# 08_-_CPU_-_SPI_I2C_SD_MMC.net
KiCad netlist of a schematic drawn in Altium Designer
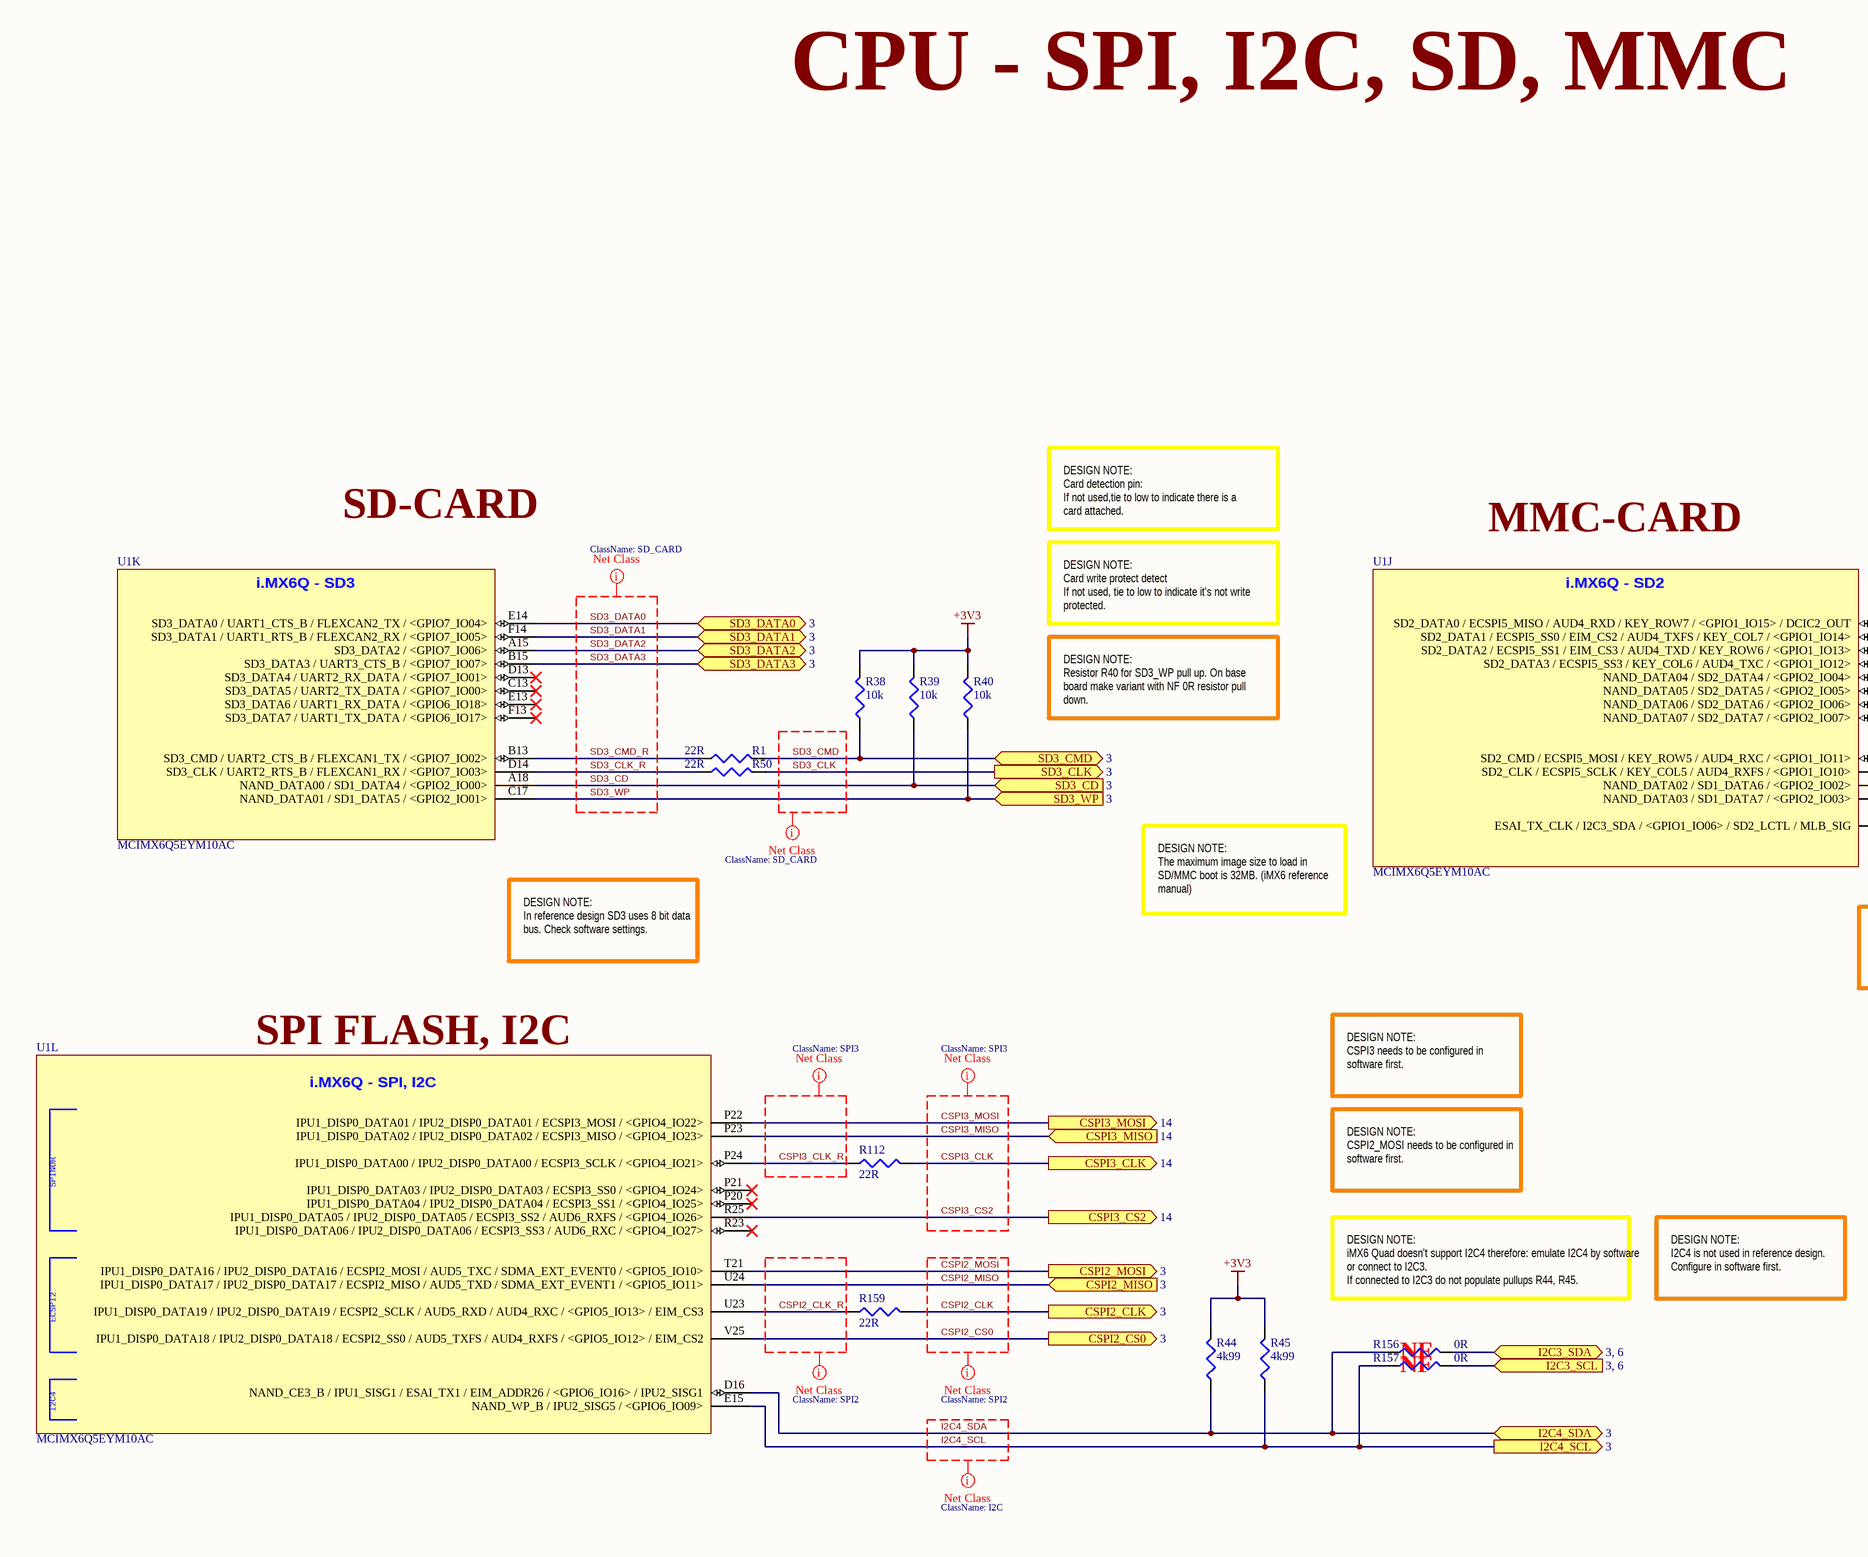
[diagram p0: [08] - CPU - SPI, I2C, SD, MMC.SchDoc, left]
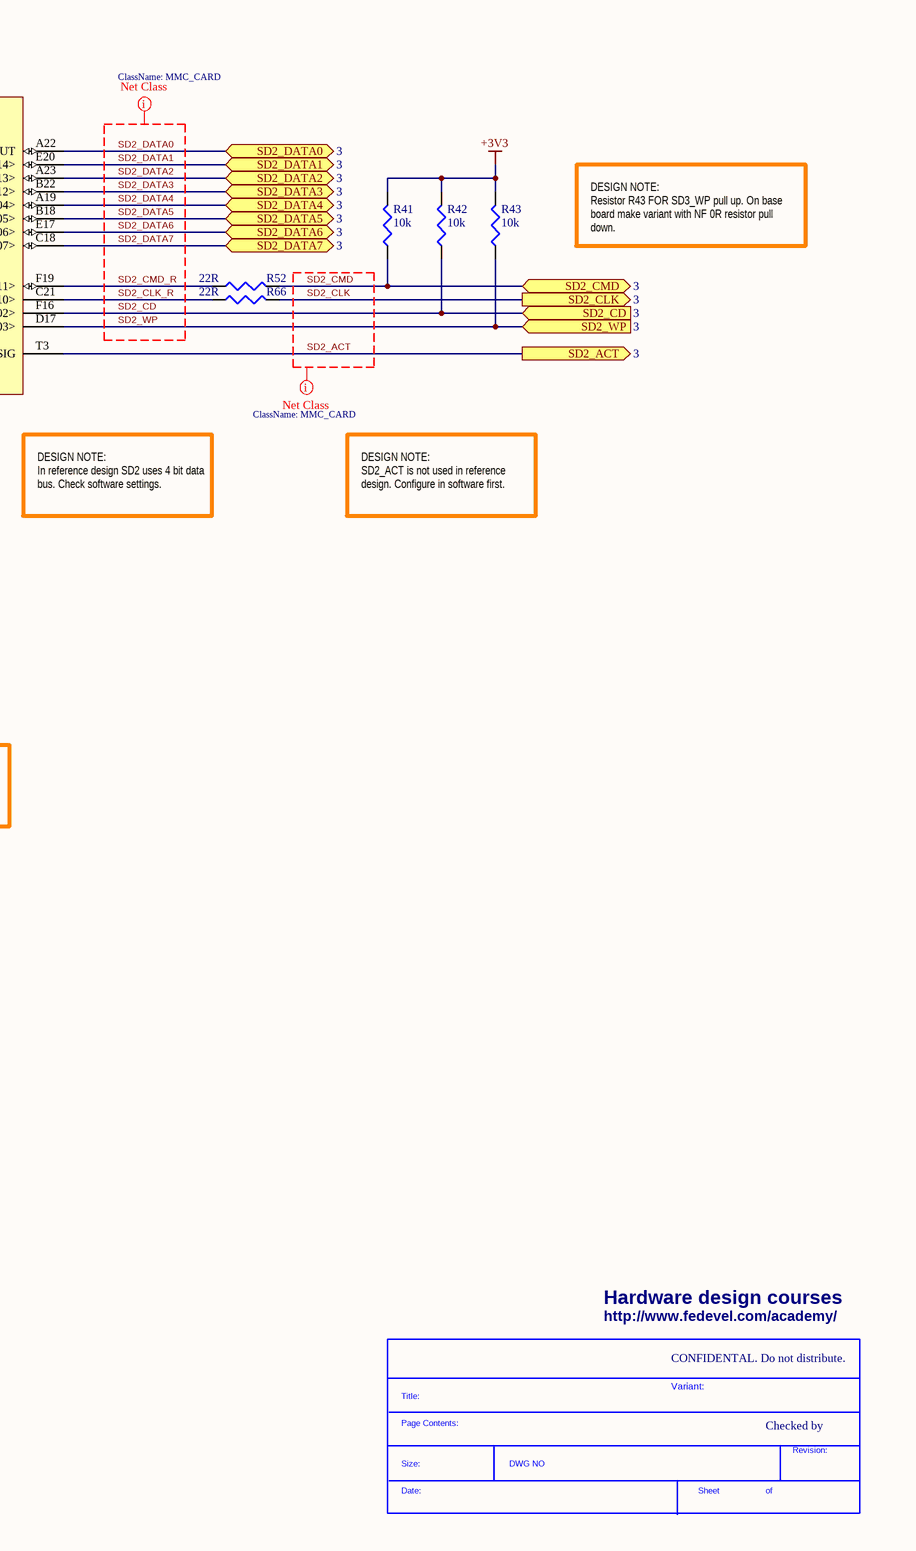
[diagram p1: [08] - CPU - SPI, I2C, SD, MMC.SchDoc, right]

(export (version "E")
  (design (tool "Eeschema 10.0.6"))
  (components
    (comp (ref "R1")
      (value "22R")
      (footprint "R0402")
      (description "RES 22.0 OHM 1/16W 1% 0402 SMD")
      (fields
        (field (name "MANUFACTURER") "Yageo")
        (field (name "MANUFACTURER PART NUMBER") "RC0402FR-0722RL")
      )
      (libsource (lib "iMX6 Rex_V1I1") (part "RC0402FR-0722RL"))
    )
    (comp (ref "R38")
      (value "10k")
      (footprint "R0402")
      (description "RES 10.0K OHM 1/16W 1% 0402 SMD")
      (fields
        (field (name "MANUFACTURER") "Yageo")
        (field (name "MANUFACTURER PART NUMBER") "RC0402FR-0710KL")
      )
      (libsource (lib "iMX6 Rex_V1I1") (part "RC0402FR-0710KL"))
    )
    (comp (ref "R39")
      (value "10k")
      (footprint "R0402")
      (description "RES 10.0K OHM 1/16W 1% 0402 SMD")
      (fields
        (field (name "MANUFACTURER") "Yageo")
        (field (name "MANUFACTURER PART NUMBER") "RC0402FR-0710KL")
      )
      (libsource (lib "iMX6 Rex_V1I1") (part "RC0402FR-0710KL"))
    )
    (comp (ref "R40")
      (value "10k")
      (footprint "R0402")
      (description "RES 10.0K OHM 1/16W 1% 0402 SMD")
      (fields
        (field (name "MANUFACTURER") "Yageo")
        (field (name "MANUFACTURER PART NUMBER") "RC0402FR-0710KL")
      )
      (libsource (lib "iMX6 Rex_V1I1") (part "RC0402FR-0710KL"))
    )
    (comp (ref "R41")
      (value "10k")
      (footprint "R0402")
      (description "RES 10.0K OHM 1/16W 1% 0402 SMD")
      (fields
        (field (name "MANUFACTURER") "Yageo")
        (field (name "MANUFACTURER PART NUMBER") "RC0402FR-0710KL")
      )
      (libsource (lib "iMX6 Rex_V1I1") (part "RC0402FR-0710KL"))
    )
    (comp (ref "R42")
      (value "10k")
      (footprint "R0402")
      (description "RES 10.0K OHM 1/16W 1% 0402 SMD")
      (fields
        (field (name "MANUFACTURER") "Yageo")
        (field (name "MANUFACTURER PART NUMBER") "RC0402FR-0710KL")
      )
      (libsource (lib "iMX6 Rex_V1I1") (part "RC0402FR-0710KL"))
    )
    (comp (ref "R43")
      (value "10k")
      (footprint "R0402")
      (description "RES 10.0K OHM 1/16W 1% 0402 SMD")
      (fields
        (field (name "MANUFACTURER") "Yageo")
        (field (name "MANUFACTURER PART NUMBER") "RC0402FR-0710KL")
      )
      (libsource (lib "iMX6 Rex_V1I1") (part "RC0402FR-0710KL"))
    )
    (comp (ref "R44")
      (value "4k99")
      (footprint "R0402")
      (description "RES TF 4.99K OHM 1% 1/16W 0402")
      (fields
        (field (name "MANUFACTURER") "Stackpole Electronics Inc")
        (field (name "MANUFACTURER PART NUMBER") "RMCF0402FT4K99")
      )
      (libsource (lib "iMX6 Rex_V1I1") (part "RMCF0402FT4K99"))
    )
    (comp (ref "R45")
      (value "4k99")
      (footprint "R0402")
      (description "RES TF 4.99K OHM 1% 1/16W 0402")
      (fields
        (field (name "MANUFACTURER") "Stackpole Electronics Inc")
        (field (name "MANUFACTURER PART NUMBER") "RMCF0402FT4K99")
      )
      (libsource (lib "iMX6 Rex_V1I1") (part "RMCF0402FT4K99"))
    )
    (comp (ref "R50")
      (value "22R")
      (footprint "R0402")
      (description "RES 22.0 OHM 1/16W 1% 0402 SMD")
      (fields
        (field (name "MANUFACTURER") "Yageo")
        (field (name "MANUFACTURER PART NUMBER") "RC0402FR-0722RL")
      )
      (libsource (lib "iMX6 Rex_V1I1") (part "RC0402FR-0722RL"))
    )
    (comp (ref "R52")
      (value "22R")
      (footprint "R0402")
      (description "RES 22.0 OHM 1/16W 1% 0402 SMD")
      (fields
        (field (name "MANUFACTURER") "Yageo")
        (field (name "MANUFACTURER PART NUMBER") "RC0402FR-0722RL")
      )
      (libsource (lib "iMX6 Rex_V1I1") (part "RC0402FR-0722RL"))
    )
    (comp (ref "R66")
      (value "22R")
      (footprint "R0402")
      (description "RES 22.0 OHM 1/16W 1% 0402 SMD")
      (fields
        (field (name "MANUFACTURER") "Yageo")
        (field (name "MANUFACTURER PART NUMBER") "RC0402FR-0722RL")
      )
      (libsource (lib "iMX6 Rex_V1I1") (part "RC0402FR-0722RL"))
    )
    (comp (ref "R112")
      (value "22R")
      (footprint "R0402")
      (description "RES 22.0 OHM 1/16W 1% 0402 SMD")
      (fields
        (field (name "MANUFACTURER") "Yageo")
        (field (name "MANUFACTURER PART NUMBER") "RC0402FR-0722RL")
      )
      (libsource (lib "iMX6 Rex_V1I1") (part "RC0402FR-0722RL"))
    )
    (comp (ref "R156")
      (value "0R")
      (footprint "R0402")
      (description "RES 0.0 OHM 1/16W 0402 SMD")
      (fields
        (field (name "MANUFACTURER") "Yageo")
        (field (name "MANUFACTURER PART NUMBER") "RC0402JR-070RL")
      )
      (libsource (lib "iMX6 Rex_V1I1") (part "RC0402JR-070RL"))
    )
    (comp (ref "R157")
      (value "0R")
      (footprint "R0402")
      (description "RES 0.0 OHM 1/16W 0402 SMD")
      (fields
        (field (name "MANUFACTURER") "Yageo")
        (field (name "MANUFACTURER PART NUMBER") "RC0402JR-070RL")
      )
      (libsource (lib "iMX6 Rex_V1I1") (part "RC0402JR-070RL"))
    )
    (comp (ref "R159")
      (value "22R")
      (footprint "R0402")
      (description "RES 22.0 OHM 1/16W 1% 0402 SMD")
      (fields
        (field (name "MANUFACTURER") "Yageo")
        (field (name "MANUFACTURER PART NUMBER") "RC0402FR-0722RL")
      )
      (libsource (lib "iMX6 Rex_V1I1") (part "RC0402FR-0722RL"))
    )
    (comp (ref "U1")
      (value "MCIMX6Q5EYM10AC")
      (footprint "PBGA624")
      (description "IC MCU 32BIT ARM QUAD 624FCBGA")
      (fields
        (field (name "MANUFACTURER") "Freescale Semiconductor")
        (field (name ".CREATOR") "MM")
        (field (name ".CHECKED PCB") "MM, checked by RF")
        (field (name ".CHECKED SCH") "MM")
      )
      (libsource (lib "iMX6 Rex_V1I1") (part "MCIMX6Q5EYM10AC"))
    )
  )
  (nets
    (net (code "1") (name "+3V3") (class "Default")
      (node (ref "R38") (pin "2") (pinfunction "2_2") (pintype "passive"))
      (node (ref "R39") (pin "2") (pinfunction "2_2") (pintype "passive"))
      (node (ref "R40") (pin "2") (pinfunction "2_2") (pintype "passive"))
      (node (ref "R41") (pin "2") (pinfunction "2_2") (pintype "passive"))
      (node (ref "R42") (pin "2") (pinfunction "2_2") (pintype "passive"))
      (node (ref "R43") (pin "2") (pinfunction "2_2") (pintype "passive"))
      (node (ref "R44") (pin "2") (pinfunction "2_2") (pintype "passive"))
      (node (ref "R45") (pin "2") (pinfunction "2_2") (pintype "passive"))
    )
    (net (code "2") (name "/CSPI2_CLK") (class "Default")
      (node (ref "R159") (pin "2") (pinfunction "2_2") (pintype "passive"))
    )
    (net (code "3") (name "/CSPI2_CLK_R") (class "Default")
      (node (ref "R159") (pin "1") (pinfunction "1_1") (pintype "passive"))
      (node (ref "U1") (pin "U23") (pinfunction "IPU1_DISP0_DATA19_/_IPU2_DISP0_DATA19_/_ECSPI2_SCLK_/_AUD5_RXD_/_AUD4_RXC_/_<GPIO5_IO13>_/_EIM_CS3_U23") (pintype "passive"))
    )
    (net (code "4") (name "/CSPI2_CS0") (class "Default")
      (node (ref "U1") (pin "V25") (pinfunction "IPU1_DISP0_DATA18_/_IPU2_DISP0_DATA18_/_ECSPI2_SS0_/_AUD5_TXFS_/_AUD4_RXFS_/_<GPIO5_IO12>_/_EIM_CS2_V25") (pintype "passive"))
    )
    (net (code "5") (name "/CSPI2_MISO") (class "Default")
      (node (ref "U1") (pin "U24") (pinfunction "IPU1_DISP0_DATA17_/_IPU2_DISP0_DATA17_/_ECSPI2_MISO_/_AUD5_TXD_/_SDMA_EXT_EVENT1_/_<GPIO5_IO11>_U24") (pintype "passive"))
    )
    (net (code "6") (name "/CSPI2_MOSI") (class "Default")
      (node (ref "U1") (pin "T21") (pinfunction "IPU1_DISP0_DATA16_/_IPU2_DISP0_DATA16_/_ECSPI2_MOSI_/_AUD5_TXC_/_SDMA_EXT_EVENT0_/_<GPIO5_IO10>_T21") (pintype "passive"))
    )
    (net (code "7") (name "/CSPI3_CLK") (class "Default")
      (node (ref "R112") (pin "2") (pinfunction "2_2") (pintype "passive"))
    )
    (net (code "8") (name "/CSPI3_CLK_R") (class "Default")
      (node (ref "R112") (pin "1") (pinfunction "1_1") (pintype "passive"))
      (node (ref "U1") (pin "P24") (pinfunction "IPU1_DISP0_DATA00_/_IPU2_DISP0_DATA00_/_ECSPI3_SCLK_/_<GPIO4_IO21>_P24") (pintype "bidirectional"))
    )
    (net (code "9") (name "/CSPI3_CS2") (class "Default")
      (node (ref "U1") (pin "R25") (pinfunction "IPU1_DISP0_DATA05_/_IPU2_DISP0_DATA05_/_ECSPI3_SS2_/_AUD6_RXFS_/_<GPIO4_IO26>_R25") (pintype "passive"))
    )
    (net (code "10") (name "/CSPI3_MISO") (class "Default")
      (node (ref "U1") (pin "P23") (pinfunction "IPU1_DISP0_DATA02_/_IPU2_DISP0_DATA02_/_ECSPI3_MISO_/_<GPIO4_IO23>_P23") (pintype "passive"))
    )
    (net (code "11") (name "/CSPI3_MOSI") (class "Default")
      (node (ref "U1") (pin "P22") (pinfunction "IPU1_DISP0_DATA01_/_IPU2_DISP0_DATA01_/_ECSPI3_MOSI_/_<GPIO4_IO22>_P22") (pintype "passive"))
    )
    (net (code "12") (name "/I2C3_SCL") (class "Default")
      (node (ref "R157") (pin "2") (pinfunction "2_2") (pintype "passive"))
    )
    (net (code "13") (name "/I2C3_SDA") (class "Default")
      (node (ref "R156") (pin "2") (pinfunction "2_2") (pintype "passive"))
    )
    (net (code "14") (name "/I2C4_SCL") (class "Default")
      (node (ref "R157") (pin "1") (pinfunction "1_1") (pintype "passive"))
      (node (ref "R45") (pin "1") (pinfunction "1_1") (pintype "passive"))
      (node (ref "U1") (pin "E15") (pinfunction "NAND_WP_B_/_IPU2_SISG5_/_<GPIO6_IO09>_E15") (pintype "passive"))
    )
    (net (code "15") (name "/I2C4_SDA") (class "Default")
      (node (ref "R156") (pin "1") (pinfunction "1_1") (pintype "passive"))
      (node (ref "R44") (pin "1") (pinfunction "1_1") (pintype "passive"))
      (node (ref "U1") (pin "D16") (pinfunction "NAND_CE3_B_/_IPU1_SISG1_/_ESAI_TX1_/_EIM_ADDR26_/_<GPIO6_IO16>_/_IPU2_SISG1_D16") (pintype "bidirectional"))
    )
    (net (code "16") (name "/SD2_ACT") (class "Default")
      (node (ref "U1") (pin "T3") (pinfunction "ESAI_TX_CLK_/_I2C3_SDA_/_<GPIO1_IO06>_/_SD2_LCTL_/_MLB_SIG_T3") (pintype "passive"))
    )
    (net (code "17") (name "/SD2_CD") (class "Default")
      (node (ref "R42") (pin "1") (pinfunction "1_1") (pintype "passive"))
      (node (ref "U1") (pin "F16") (pinfunction "NAND_DATA02_/_SD1_DATA6_/_<GPIO2_IO02>_F16") (pintype "passive"))
    )
    (net (code "18") (name "/SD2_CLK") (class "Default")
      (node (ref "R66") (pin "2") (pinfunction "2_2") (pintype "passive"))
    )
    (net (code "19") (name "/SD2_CLK_R") (class "Default")
      (node (ref "R66") (pin "1") (pinfunction "1_1") (pintype "passive"))
      (node (ref "U1") (pin "C21") (pinfunction "SD2_CLK_/_ECSPI5_SCLK_/_KEY_COL5_/_AUD4_RXFS_/_<GPIO1_IO10>_C21") (pintype "passive"))
    )
    (net (code "20") (name "/SD2_CMD") (class "Default")
      (node (ref "R41") (pin "1") (pinfunction "1_1") (pintype "passive"))
      (node (ref "R52") (pin "2") (pinfunction "2_2") (pintype "passive"))
    )
    (net (code "21") (name "/SD2_CMD_R") (class "Default")
      (node (ref "R52") (pin "1") (pinfunction "1_1") (pintype "passive"))
      (node (ref "U1") (pin "F19") (pinfunction "SD2_CMD_/_ECSPI5_MOSI_/_KEY_ROW5_/_AUD4_RXC_/_<GPIO1_IO11>_F19") (pintype "bidirectional"))
    )
    (net (code "22") (name "/SD2_DATA0") (class "Default")
      (node (ref "U1") (pin "A22") (pinfunction "SD2_DATA0_/_ECSPI5_MISO_/_AUD4_RXD_/_KEY_ROW7_/_<GPIO1_IO15>_/_DCIC2_OUT_A22") (pintype "bidirectional"))
    )
    (net (code "23") (name "/SD2_DATA1") (class "Default")
      (node (ref "U1") (pin "E20") (pinfunction "SD2_DATA1_/_ECSPI5_SS0_/_EIM_CS2_/_AUD4_TXFS_/_KEY_COL7_/_<GPIO1_IO14>_E20") (pintype "bidirectional"))
    )
    (net (code "24") (name "/SD2_DATA2") (class "Default")
      (node (ref "U1") (pin "A23") (pinfunction "SD2_DATA2_/_ECSPI5_SS1_/_EIM_CS3_/_AUD4_TXD_/_KEY_ROW6_/_<GPIO1_IO13>_A23") (pintype "bidirectional"))
    )
    (net (code "25") (name "/SD2_DATA3") (class "Default")
      (node (ref "U1") (pin "B22") (pinfunction "SD2_DATA3_/_ECSPI5_SS3_/_KEY_COL6_/_AUD4_TXC_/_<GPIO1_IO12>_B22") (pintype "bidirectional"))
    )
    (net (code "26") (name "/SD2_DATA4") (class "Default")
      (node (ref "U1") (pin "A19") (pinfunction "NAND_DATA04_/_SD2_DATA4_/_<GPIO2_IO04>_A19") (pintype "bidirectional"))
    )
    (net (code "27") (name "/SD2_DATA5") (class "Default")
      (node (ref "U1") (pin "B18") (pinfunction "NAND_DATA05_/_SD2_DATA5_/_<GPIO2_IO05>_B18") (pintype "bidirectional"))
    )
    (net (code "28") (name "/SD2_DATA6") (class "Default")
      (node (ref "U1") (pin "E17") (pinfunction "NAND_DATA06_/_SD2_DATA6_/_<GPIO2_IO06>_E17") (pintype "bidirectional"))
    )
    (net (code "29") (name "/SD2_DATA7") (class "Default")
      (node (ref "U1") (pin "C18") (pinfunction "NAND_DATA07_/_SD2_DATA7_/_<GPIO2_IO07>_C18") (pintype "bidirectional"))
    )
    (net (code "30") (name "/SD2_WP") (class "Default")
      (node (ref "R43") (pin "1") (pinfunction "1_1") (pintype "passive"))
      (node (ref "U1") (pin "D17") (pinfunction "NAND_DATA03_/_SD1_DATA7_/_<GPIO2_IO03>_D17") (pintype "passive"))
    )
    (net (code "31") (name "/SD3_CD") (class "Default")
      (node (ref "R39") (pin "1") (pinfunction "1_1") (pintype "passive"))
      (node (ref "U1") (pin "A18") (pinfunction "NAND_DATA00_/_SD1_DATA4_/_<GPIO2_IO00>_A18") (pintype "passive"))
    )
    (net (code "32") (name "/SD3_CLK") (class "Default")
      (node (ref "R50") (pin "2") (pinfunction "2_2") (pintype "passive"))
    )
    (net (code "33") (name "/SD3_CLK_R") (class "Default")
      (node (ref "R50") (pin "1") (pinfunction "1_1") (pintype "passive"))
      (node (ref "U1") (pin "D14") (pinfunction "SD3_CLK_/_UART2_RTS_B_/_FLEXCAN1_RX_/_<GPIO7_IO03>_D14") (pintype "passive"))
    )
    (net (code "34") (name "/SD3_CMD") (class "Default")
      (node (ref "R1") (pin "2") (pinfunction "2_2") (pintype "passive"))
      (node (ref "R38") (pin "1") (pinfunction "1_1") (pintype "passive"))
    )
    (net (code "35") (name "/SD3_CMD_R") (class "Default")
      (node (ref "R1") (pin "1") (pinfunction "1_1") (pintype "passive"))
      (node (ref "U1") (pin "B13") (pinfunction "SD3_CMD_/_UART2_CTS_B_/_FLEXCAN1_TX_/_<GPIO7_IO02>_B13") (pintype "bidirectional"))
    )
    (net (code "36") (name "/SD3_DATA0") (class "Default")
      (node (ref "U1") (pin "E14") (pinfunction "SD3_DATA0_/_UART1_CTS_B_/_FLEXCAN2_TX_/_<GPIO7_IO04>_E14") (pintype "bidirectional"))
    )
    (net (code "37") (name "/SD3_DATA1") (class "Default")
      (node (ref "U1") (pin "F14") (pinfunction "SD3_DATA1_/_UART1_RTS_B_/_FLEXCAN2_RX_/_<GPIO7_IO05>_F14") (pintype "bidirectional"))
    )
    (net (code "38") (name "/SD3_DATA2") (class "Default")
      (node (ref "U1") (pin "A15") (pinfunction "SD3_DATA2_/_<GPIO7_IO06>_A15") (pintype "bidirectional"))
    )
    (net (code "39") (name "/SD3_DATA3") (class "Default")
      (node (ref "U1") (pin "B15") (pinfunction "SD3_DATA3_/_UART3_CTS_B_/_<GPIO7_IO07>_B15") (pintype "bidirectional"))
    )
    (net (code "40") (name "/SD3_WP") (class "Default")
      (node (ref "R40") (pin "1") (pinfunction "1_1") (pintype "passive"))
      (node (ref "U1") (pin "C17") (pinfunction "NAND_DATA01_/_SD1_DATA5_/_<GPIO2_IO01>_C17") (pintype "passive"))
    )
    (net (code "41") (name "unconnected-(U1K-SD3_DATA4_{slash}_UART2_RX_DATA_{slash}_<GPIO7_IO01>-PadD13)") (class "Default")
      (node (ref "U1") (pin "D13") (pinfunction "SD3_DATA4_/_UART2_RX_DATA_/_<GPIO7_IO01>_D13") (pintype "bidirectional+no_connect"))
    )
    (net (code "42") (name "unconnected-(U1K-SD3_DATA5_{slash}_UART2_TX_DATA_{slash}_<GPIO7_IO00>-PadC13)") (class "Default")
      (node (ref "U1") (pin "C13") (pinfunction "SD3_DATA5_/_UART2_TX_DATA_/_<GPIO7_IO00>_C13") (pintype "bidirectional+no_connect"))
    )
    (net (code "43") (name "unconnected-(U1K-SD3_DATA6_{slash}_UART1_RX_DATA_{slash}_<GPIO6_IO18>-PadE13)") (class "Default")
      (node (ref "U1") (pin "E13") (pinfunction "SD3_DATA6_/_UART1_RX_DATA_/_<GPIO6_IO18>_E13") (pintype "bidirectional+no_connect"))
    )
    (net (code "44") (name "unconnected-(U1K-SD3_DATA7_{slash}_UART1_TX_DATA_{slash}_<GPIO6_IO17>-PadF13)") (class "Default")
      (node (ref "U1") (pin "F13") (pinfunction "SD3_DATA7_/_UART1_TX_DATA_/_<GPIO6_IO17>_F13") (pintype "bidirectional+no_connect"))
    )
    (net (code "45") (name "unconnected-(U1L-IPU1_DISP0_DATA03_{slash}_IPU2_DISP0_DATA03_{slash}_ECSPI3_SS0_{slash}_<GPIO4_IO24>-PadP21)") (class "Default")
      (node (ref "U1") (pin "P21") (pinfunction "IPU1_DISP0_DATA03_/_IPU2_DISP0_DATA03_/_ECSPI3_SS0_/_<GPIO4_IO24>_P21") (pintype "bidirectional+no_connect"))
    )
    (net (code "46") (name "unconnected-(U1L-IPU1_DISP0_DATA04_{slash}_IPU2_DISP0_DATA04_{slash}_ECSPI3_SS1_{slash}_<GPIO4_IO25>-PadP20)") (class "Default")
      (node (ref "U1") (pin "P20") (pinfunction "IPU1_DISP0_DATA04_/_IPU2_DISP0_DATA04_/_ECSPI3_SS1_/_<GPIO4_IO25>_P20") (pintype "bidirectional+no_connect"))
    )
    (net (code "47") (name "unconnected-(U1L-IPU1_DISP0_DATA06_{slash}_IPU2_DISP0_DATA06_{slash}_ECSPI3_SS3_{slash}_AUD6_RXC_{slash}_<GPIO4_IO27>-PadR23)") (class "Default")
      (node (ref "U1") (pin "R23") (pinfunction "IPU1_DISP0_DATA06_/_IPU2_DISP0_DATA06_/_ECSPI3_SS3_/_AUD6_RXC_/_<GPIO4_IO27>_R23") (pintype "bidirectional+no_connect"))
    )
  )
)
